# MainBoard_Power.net
KiCad netlist of a schematic drawn in Altium Designer
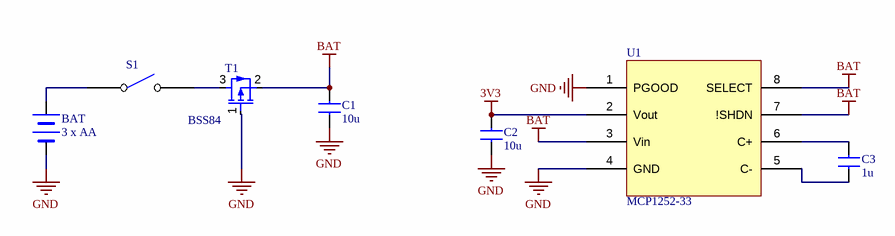
[diagram p0: MainBoard_Power.SchDoc]

(export (version "E")
  (design (tool "Eeschema 10.0.6"))
  (components
    (comp (ref "BAT") (value "3 x AA") (footprint "POWER2") (libsource (lib "DEVICE_HSLU") (part "BATTERY")))
    (comp (ref "C1")
      (value "10u")
      (footprint "0805_C")
      (description "Normaler Kondensator")
      (libsource (lib "MainBoard") (part "C?"))
    )
    (comp (ref "C2")
      (value "10u")
      (footprint "0805_C")
      (description "Normaler Kondensator")
      (libsource (lib "MainBoard") (part "C?"))
    )
    (comp (ref "C3")
      (value "1u")
      (footprint "0805_C")
      (description "Normaler Kondensator")
      (libsource (lib "MainBoard") (part "C?"))
    )
    (comp (ref "S1") (value "SW SPST") (footprint "SIP2") (libsource (lib "DEVICE_HSLU") (part "SW SPST")))
    (comp (ref "T1")
      (value "BSS84")
      (footprint "SOT23-3")
      (description "MOSFET-P 1G,2D,3S (Diode)")
      (libsource (lib "Sch_Lib") (part "MOSFET-P 1G,2D,3S (Diode)"))
    )
    (comp (ref "U1") (value "MCP1252-33") (footprint "MSOP8") (libsource (lib "MainBoard") (part "VOLTREG")))
  )
  (nets
    (net (code "1") (name "3V3") (class "Default")
      (node (ref "C2") (pin "2") (pinfunction "2_2") (pintype "passive"))
      (node (ref "U1") (pin "2") (pinfunction "Vout_2") (pintype "passive"))
    )
    (net (code "2") (name "BAT") (class "Default")
      (node (ref "C1") (pin "2") (pinfunction "2_2") (pintype "passive"))
      (node (ref "T1") (pin "2") (pinfunction "S_2") (pintype "passive"))
      (node (ref "U1") (pin "3") (pinfunction "Vin_3") (pintype "passive"))
      (node (ref "U1") (pin "7") (pinfunction "!SHDN_7") (pintype "passive"))
      (node (ref "U1") (pin "8") (pinfunction "SELECT_8") (pintype "passive"))
    )
    (net (code "3") (name "GND") (class "Default")
      (node (ref "BAT") (pin "2") (pintype "passive"))
      (node (ref "C1") (pin "1") (pinfunction "1_1") (pintype "passive"))
      (node (ref "C2") (pin "1") (pinfunction "1_1") (pintype "passive"))
      (node (ref "T1") (pin "1") (pinfunction "G_1") (pintype "passive"))
      (node (ref "U1") (pin "1") (pinfunction "PGOOD_1") (pintype "passive"))
      (node (ref "U1") (pin "4") (pinfunction "GND_4") (pintype "passive"))
    )
    (net (code "4") (name "Net-(S1-COMMON)") (class "Default")
      (node (ref "BAT") (pin "1") (pintype "passive"))
      (node (ref "S1") (pin "1") (pinfunction "COMMON_1") (pintype "passive"))
    )
    (net (code "5") (name "Net-(S1-NO)") (class "Default")
      (node (ref "S1") (pin "2") (pinfunction "NO_2") (pintype "passive"))
      (node (ref "T1") (pin "3") (pinfunction "D_3") (pintype "passive"))
    )
    (net (code "6") (name "Net-(U1-C+)") (class "Default")
      (node (ref "C3") (pin "2") (pinfunction "2_2") (pintype "passive"))
      (node (ref "U1") (pin "6") (pinfunction "C+_6") (pintype "passive"))
    )
    (net (code "7") (name "Net-(U1-C-)") (class "Default")
      (node (ref "C3") (pin "1") (pinfunction "1_1") (pintype "passive"))
      (node (ref "U1") (pin "5") (pinfunction "C-_5") (pintype "passive"))
    )
  )
)
